# RelayDelayTiny.net
KiCad netlist of a schematic drawn in EAGLE
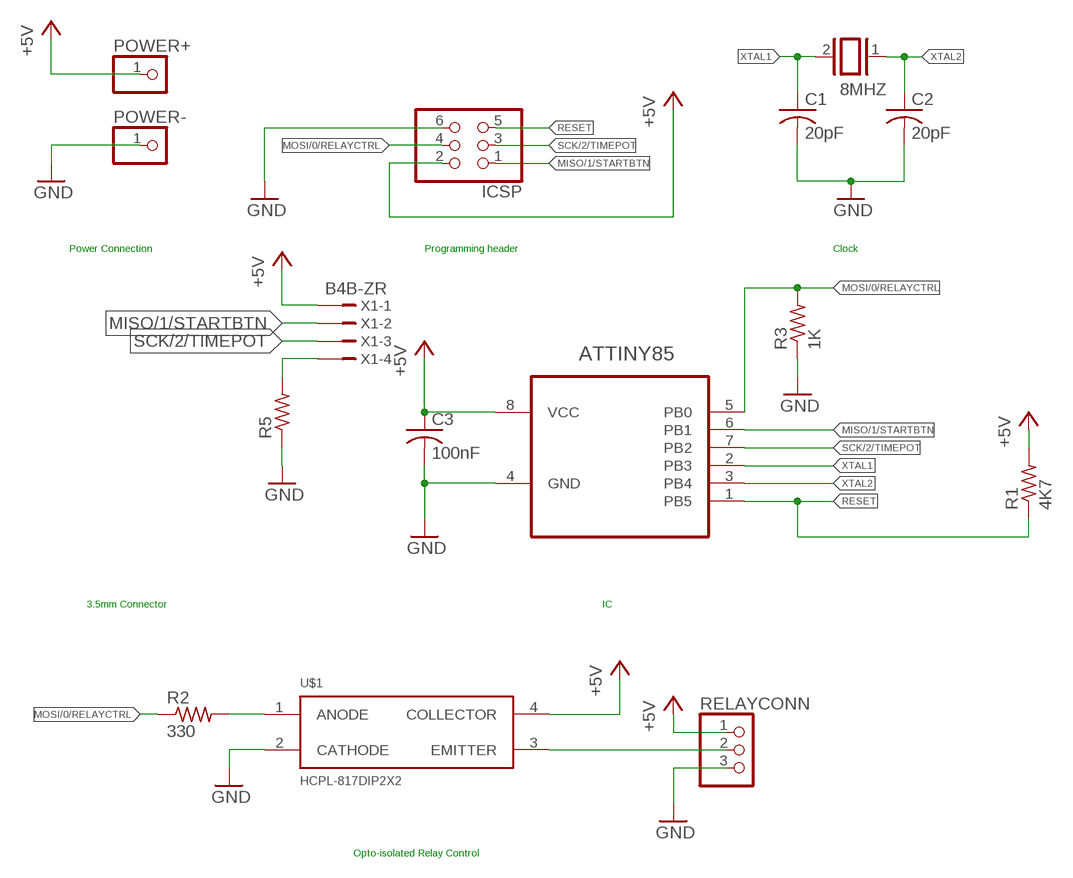
[diagram p0: schematic, sheet 1]

(export (version "E")
  (design (tool "Eeschema 10.0.6"))
  (components
    (comp (ref "8MHZ")
      (value "XTAL/S")
      (footprint "eagle-import:QS")
      (libsource (lib "eagle-import") (part "XTAL/S"))
    )
    (comp (ref "ATTINY85")
      (value "ATTINY85-20SU")
      (footprint "eagle-import:SOIC127P798X216-8N")
      (libsource (lib "eagle-import") (part "ATTINY85-20SU"))
    )
    (comp (ref "C1")
      (value "20pF")
      (footprint "eagle-import:C0805")
      (libsource (lib "eagle-import") (part "C-USC0805"))
    )
    (comp (ref "C2")
      (value "20pF")
      (footprint "eagle-import:C0805")
      (libsource (lib "eagle-import") (part "C-USC0805"))
    )
    (comp (ref "C3")
      (value "100nF")
      (footprint "eagle-import:C0805")
      (libsource (lib "eagle-import") (part "C-USC0805"))
    )
    (comp (ref "ICSP")
      (value "PINHD-2X3")
      (footprint "eagle-import:2X03")
      (libsource (lib "eagle-import") (part "PINHD-2X3"))
    )
    (comp (ref "POWER+")
      (value "PINHD-1X1")
      (footprint "eagle-import:1X01")
      (libsource (lib "eagle-import") (part "PINHD-1X1"))
    )
    (comp (ref "POWER-")
      (value "PINHD-1X1")
      (footprint "eagle-import:1X01")
      (libsource (lib "eagle-import") (part "PINHD-1X1"))
    )
    (comp (ref "R1")
      (value "4K7")
      (footprint "eagle-import:R0805")
      (libsource (lib "eagle-import") (part "resistor_R-US_R0805"))
    )
    (comp (ref "R2")
      (value "330")
      (footprint "eagle-import:M0805")
      (libsource (lib "eagle-import") (part "resistor_R-US_M0805"))
    )
    (comp (ref "R3")
      (value "1K")
      (footprint "eagle-import:M0805")
      (libsource (lib "eagle-import") (part "resistor_R-US_M0805"))
    )
    (comp (ref "R5")
      (value "R-US_R0805")
      (footprint "eagle-import:R0805")
      (libsource (lib "eagle-import") (part "R-US_R0805"))
    )
    (comp (ref "RELAYCONN")
      (value "PINHD-1X3")
      (footprint "eagle-import:1X03")
      (libsource (lib "eagle-import") (part "PINHD-1X3"))
    )
    (comp (ref "U$1")
      (value "HCPL-817DIP2X2")
      (footprint "eagle-import:DIP")
      (libsource (lib "eagle-import") (part "HCPL-817DIP2X2"))
    )
    (comp (ref "X1")
      (value "B4B-ZR")
      (footprint "eagle-import:B4B-ZR")
      (fields (field (name "MF") "FARNELL") (field (name "MPN") "B4B-ZR(LF)(SN)"))
      (libsource (lib "eagle-import") (part "?4B-ZRB"))
    )
  )
  (nets
    (net (code "1") (name "+5V") (class "Default")
      (node (ref "ATTINY85") (pin "8") (pinfunction "VCC_8") (pintype "power_in"))
      (node (ref "C3") (pin "1") (pinfunction "1_1") (pintype "passive"))
      (node (ref "ICSP") (pin "2") (pinfunction "2_2") (pintype "passive"))
      (node (ref "POWER+") (pin "1") (pinfunction "1_1") (pintype "passive"))
      (node (ref "R1") (pin "2") (pinfunction "2_2") (pintype "passive"))
      (node (ref "RELAYCONN") (pin "1") (pinfunction "1_1") (pintype "passive"))
      (node (ref "U$1") (pin "4") (pinfunction "COLLECTOR_4") (pintype "bidirectional"))
      (node (ref "X1") (pin "1") (pinfunction "1_1") (pintype "passive"))
    )
    (net (code "2") (name "GND") (class "Default")
      (node (ref "ATTINY85") (pin "4") (pinfunction "GND_4") (pintype "passive"))
      (node (ref "C1") (pin "2") (pinfunction "2_2") (pintype "passive"))
      (node (ref "C2") (pin "2") (pinfunction "2_2") (pintype "passive"))
      (node (ref "C3") (pin "2") (pinfunction "2_2") (pintype "passive"))
      (node (ref "ICSP") (pin "6") (pinfunction "6_6") (pintype "passive"))
      (node (ref "POWER-") (pin "1") (pinfunction "1_1") (pintype "passive"))
      (node (ref "R3") (pin "1") (pinfunction "1_1") (pintype "passive"))
      (node (ref "R5") (pin "1") (pinfunction "1_1") (pintype "passive"))
      (node (ref "RELAYCONN") (pin "3") (pinfunction "3_3") (pintype "passive"))
      (node (ref "U$1") (pin "2") (pinfunction "CATHODE_2") (pintype "bidirectional"))
    )
    (net (code "3") (name "MISO{slash}1{slash}STARTBTN") (class "Default")
      (node (ref "ATTINY85") (pin "6") (pinfunction "PB1_6") (pintype "bidirectional"))
      (node (ref "ICSP") (pin "1") (pinfunction "1_1") (pintype "passive"))
      (node (ref "X1") (pin "2") (pinfunction "1_2") (pintype "passive"))
    )
    (net (code "4") (name "MOSI{slash}0{slash}RELAYCTRL") (class "Default")
      (node (ref "ATTINY85") (pin "5") (pinfunction "PB0_5") (pintype "bidirectional"))
      (node (ref "ICSP") (pin "4") (pinfunction "4_4") (pintype "passive"))
      (node (ref "R2") (pin "1") (pinfunction "1_1") (pintype "passive"))
      (node (ref "R3") (pin "2") (pinfunction "2_2") (pintype "passive"))
    )
    (net (code "5") (name "Net-(U$1-ANODE)") (class "Default")
      (node (ref "R2") (pin "2") (pinfunction "2_2") (pintype "passive"))
      (node (ref "U$1") (pin "1") (pinfunction "ANODE_1") (pintype "bidirectional"))
    )
    (net (code "6") (name "Net-(U$1-EMITTER)") (class "Default")
      (node (ref "RELAYCONN") (pin "2") (pinfunction "2_2") (pintype "passive"))
      (node (ref "U$1") (pin "3") (pinfunction "EMITTER_3") (pintype "bidirectional"))
    )
    (net (code "7") (name "Net-(X1D-1)") (class "Default")
      (node (ref "R5") (pin "2") (pinfunction "2_2") (pintype "passive"))
      (node (ref "X1") (pin "4") (pinfunction "1_4") (pintype "passive"))
    )
    (net (code "8") (name "RESET") (class "Default")
      (node (ref "ATTINY85") (pin "1") (pinfunction "PB5_1") (pintype "bidirectional"))
      (node (ref "ICSP") (pin "5") (pinfunction "5_5") (pintype "passive"))
      (node (ref "R1") (pin "1") (pinfunction "1_1") (pintype "passive"))
    )
    (net (code "9") (name "SCK{slash}2{slash}TIMEPOT") (class "Default")
      (node (ref "ATTINY85") (pin "7") (pinfunction "PB2_7") (pintype "bidirectional"))
      (node (ref "ICSP") (pin "3") (pinfunction "3_3") (pintype "passive"))
      (node (ref "X1") (pin "3") (pinfunction "1_3") (pintype "passive"))
    )
    (net (code "10") (name "XTAL1") (class "Default")
      (node (ref "8MHZ") (pin "2") (pinfunction "2_2") (pintype "passive"))
      (node (ref "ATTINY85") (pin "2") (pinfunction "PB3_2") (pintype "bidirectional"))
      (node (ref "C1") (pin "1") (pinfunction "1_1") (pintype "passive"))
    )
    (net (code "11") (name "XTAL2") (class "Default")
      (node (ref "8MHZ") (pin "1") (pinfunction "1_1") (pintype "passive"))
      (node (ref "ATTINY85") (pin "3") (pinfunction "PB4_3") (pintype "bidirectional"))
      (node (ref "C2") (pin "1") (pinfunction "1_1") (pintype "passive"))
    )
  )
)
